# RBPZ_DynamixelMaxim.net
KiCad netlist of a schematic drawn in EAGLE
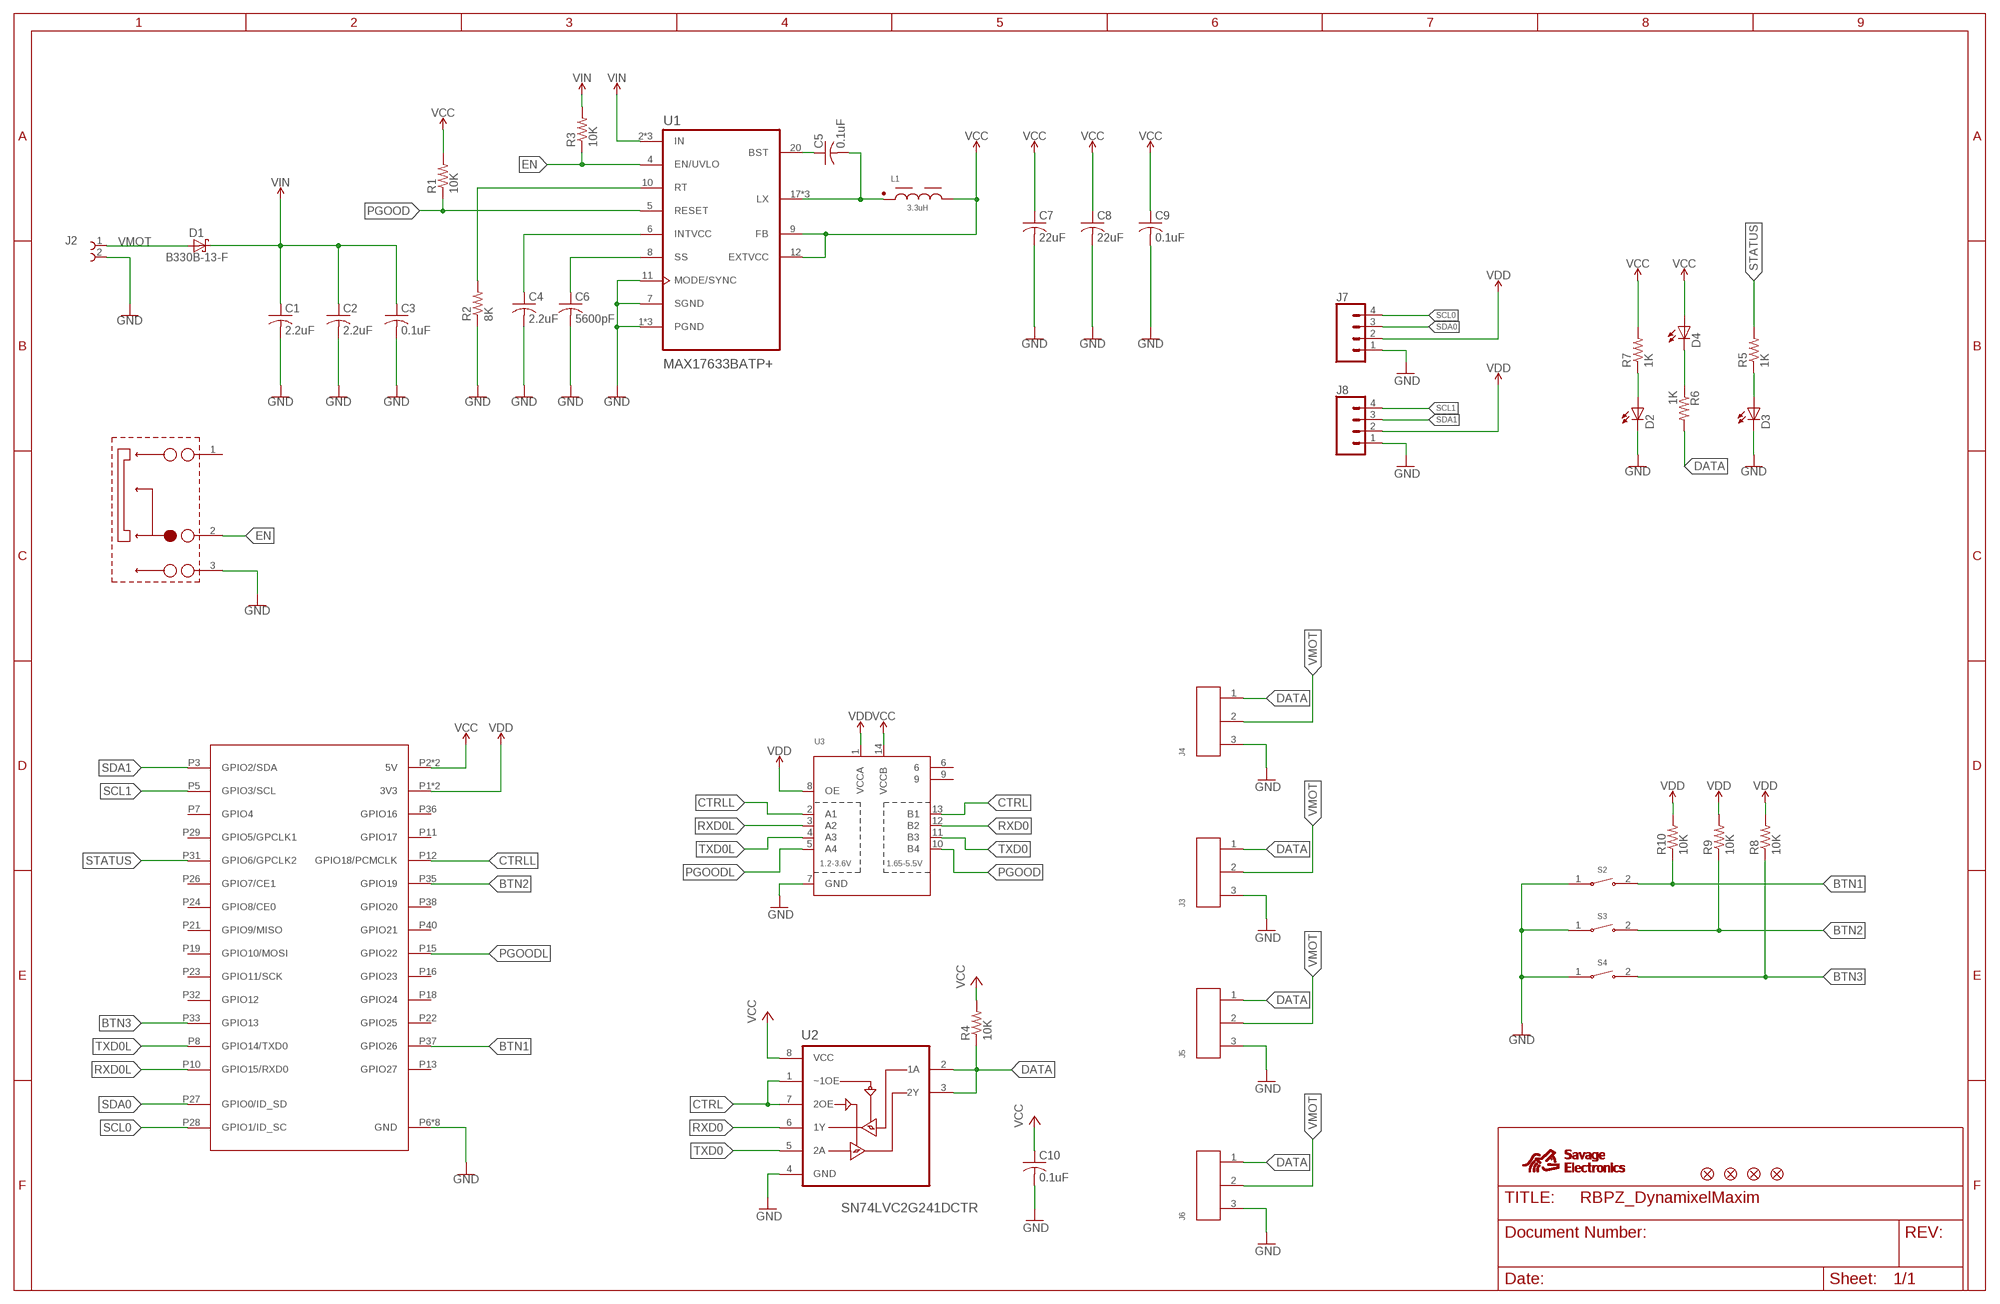
[diagram p0: schematic, sheet 1]

(export (version "E")
  (design (tool "Eeschema 10.0.6"))
  (components
    (comp (ref "C1")
      (value "2.2uF")
      (footprint "eagle-import:C1210")
      (libsource (lib "eagle-import") (part "C-USC1210"))
    )
    (comp (ref "C2")
      (value "2.2uF")
      (footprint "eagle-import:C1210")
      (libsource (lib "eagle-import") (part "C-USC1210"))
    )
    (comp (ref "C3")
      (value "0.1uF")
      (footprint "eagle-import:C0805")
      (libsource (lib "eagle-import") (part "C-USC0805"))
    )
    (comp (ref "C4")
      (value "2.2uF")
      (footprint "eagle-import:C1206")
      (libsource (lib "eagle-import") (part "C-USC1206"))
    )
    (comp (ref "C5")
      (value "0.1uF")
      (footprint "eagle-import:C0603")
      (libsource (lib "eagle-import") (part "C-USC0603"))
    )
    (comp (ref "C6")
      (value "5600pF")
      (footprint "eagle-import:C0805")
      (libsource (lib "eagle-import") (part "C-USC0805"))
    )
    (comp (ref "C7")
      (value "22uF")
      (footprint "eagle-import:C1210")
      (libsource (lib "eagle-import") (part "C-USC1210"))
    )
    (comp (ref "C8")
      (value "22uF")
      (footprint "eagle-import:C1210")
      (libsource (lib "eagle-import") (part "C-USC1210"))
    )
    (comp (ref "C9")
      (value "0.1uF")
      (footprint "eagle-import:C0805")
      (libsource (lib "eagle-import") (part "C-USC0805"))
    )
    (comp (ref "C10")
      (value "0.1uF")
      (footprint "eagle-import:C0603")
      (libsource (lib "eagle-import") (part "C-USC0603"))
    )
    (comp (ref "D1")
      (value "B330B-13-F")
      (footprint "eagle-import:DIONM4336X250N")
      (libsource (lib "eagle-import") (part "B330B-13-F"))
    )
    (comp (ref "D2")
      (value "LEDCHIP-LED0805")
      (footprint "eagle-import:CHIP-LED0805")
      (libsource (lib "eagle-import") (part "LEDCHIP-LED0805"))
    )
    (comp (ref "D3")
      (value "LEDCHIP-LED0805")
      (footprint "eagle-import:CHIP-LED0805")
      (libsource (lib "eagle-import") (part "LEDCHIP-LED0805"))
    )
    (comp (ref "D4")
      (value "LEDCHIP-LED0805")
      (footprint "eagle-import:CHIP-LED0805")
      (libsource (lib "eagle-import") (part "LEDCHIP-LED0805"))
    )
    (comp (ref "FID1")
      (value "FIDUCIAL\"\"")
      (footprint "eagle-import:FIDUCIAL_1MM")
      (libsource (lib "eagle-import") (part "FIDUCIAL{dblquote}{dblquote}"))
    )
    (comp (ref "FID2")
      (value "FIDUCIAL\"\"")
      (footprint "eagle-import:FIDUCIAL_1MM")
      (libsource (lib "eagle-import") (part "FIDUCIAL{dblquote}{dblquote}"))
    )
    (comp (ref "FID3")
      (value "FIDUCIAL\"\"")
      (footprint "eagle-import:FIDUCIAL_1MM")
      (libsource (lib "eagle-import") (part "FIDUCIAL{dblquote}{dblquote}"))
    )
    (comp (ref "FID4")
      (value "FIDUCIAL\"\"")
      (footprint "eagle-import:FIDUCIAL_1MM")
      (libsource (lib "eagle-import") (part "FIDUCIAL{dblquote}{dblquote}"))
    )
    (comp (ref "J1")
      (value "RBPZERO")
      (footprint "eagle-import:61004021821_RASPBERRYPIZERO")
      (libsource (lib "eagle-import") (part "RBPZERO"))
    )
    (comp (ref "J2")
      (value "691137910002")
      (footprint "eagle-import:691137910002")
      (libsource (lib "eagle-import") (part "691137910002"))
    )
    (comp (ref "J3")
      (value "64600311622")
      (footprint "eagle-import:64600311622")
      (libsource (lib "eagle-import") (part "64600311622"))
    )
    (comp (ref "J4")
      (value "64600311622")
      (footprint "eagle-import:64600311622")
      (libsource (lib "eagle-import") (part "64600311622"))
    )
    (comp (ref "J5")
      (value "64600311622")
      (footprint "eagle-import:64600311622")
      (libsource (lib "eagle-import") (part "64600311622"))
    )
    (comp (ref "J6")
      (value "64600311622")
      (footprint "eagle-import:64600311622")
      (libsource (lib "eagle-import") (part "64600311622"))
    )
    (comp (ref "J7")
      (value "CONN_04SMD2")
      (footprint "eagle-import:1X04_1MM_RA")
      (libsource (lib "eagle-import") (part "CONN_04SMD2"))
    )
    (comp (ref "J8")
      (value "CONN_04SMD2")
      (footprint "eagle-import:1X04_1MM_RA")
      (libsource (lib "eagle-import") (part "CONN_04SMD2"))
    )
    (comp (ref "L1")
      (value "3.3uH")
      (footprint "eagle-import:WE-SPC_48XX")
      (libsource (lib "eagle-import") (part "WE-SPC_4828_74408942012"))
    )
    (comp (ref "R1")
      (value "10K")
      (footprint "eagle-import:R0805")
      (libsource (lib "eagle-import") (part "R-US_R0805"))
    )
    (comp (ref "R2")
      (value "8K")
      (footprint "eagle-import:R0805")
      (libsource (lib "eagle-import") (part "R-US_R0805"))
    )
    (comp (ref "R3")
      (value "10K")
      (footprint "eagle-import:R0805")
      (libsource (lib "eagle-import") (part "R-US_R0805"))
    )
    (comp (ref "R4")
      (value "10K")
      (footprint "eagle-import:R0805")
      (libsource (lib "eagle-import") (part "R-US_R0805"))
    )
    (comp (ref "R5")
      (value "1K")
      (footprint "eagle-import:R0805")
      (libsource (lib "eagle-import") (part "R-US_R0805"))
    )
    (comp (ref "R6")
      (value "1K")
      (footprint "eagle-import:R0805")
      (libsource (lib "eagle-import") (part "R-US_R0805"))
    )
    (comp (ref "R7")
      (value "1K")
      (footprint "eagle-import:R0805")
      (libsource (lib "eagle-import") (part "R-US_R0805"))
    )
    (comp (ref "R8")
      (value "10K")
      (footprint "eagle-import:R0805")
      (libsource (lib "eagle-import") (part "R-US_R0805"))
    )
    (comp (ref "R9")
      (value "10K")
      (footprint "eagle-import:R0805")
      (libsource (lib "eagle-import") (part "R-US_R0805"))
    )
    (comp (ref "R10")
      (value "10K")
      (footprint "eagle-import:R0805")
      (libsource (lib "eagle-import") (part "R-US_R0805"))
    )
    (comp (ref "S1")
      (value "450404015514")
      (footprint "eagle-import:450404015514")
      (libsource (lib "eagle-import") (part "450404015514"))
    )
    (comp (ref "S2")
      (value "434123025826-2PIN")
      (footprint "eagle-import:434123025826-2PIN")
      (libsource (lib "eagle-import") (part "434123025826-2PIN"))
    )
    (comp (ref "S3")
      (value "434123025826-2PIN")
      (footprint "eagle-import:434123025826-2PIN")
      (libsource (lib "eagle-import") (part "434123025826-2PIN"))
    )
    (comp (ref "S4")
      (value "434123025826-2PIN")
      (footprint "eagle-import:434123025826-2PIN")
      (libsource (lib "eagle-import") (part "434123025826-2PIN"))
    )
    (comp (ref "U1")
      (value "MAX17633BATP+")
      (footprint "eagle-import:QFN50P400X400X80-21N")
      (fields (field (name "MF") "Maxim Integrated") (field (name "MP") "MAX32660GTP+T"))
      (libsource (lib "eagle-import") (part "MAX17633BATP+"))
    )
    (comp (ref "U2")
      (value "SN74LVC2G241DCTR")
      (footprint "eagle-import:SOP65P400X130-8N")
      (fields (field (name "MF") "Texas Instruments") (field (name "MP") "SN74LVC2G241"))
      (libsource (lib "eagle-import") (part "SN74LVC2G241"))
    )
    (comp (ref "U3")
      (value "TXB0104PWR")
      (footprint "eagle-import:TSSOP14")
      (libsource (lib "eagle-import") (part "TXB0104PWR"))
    )
  )
  (nets
    (net (code "1") (name "BTN1") (class "Default")
      (node (ref "J1") (pin "P37") (pinfunction "GPIO26_P37") (pintype "bidirectional"))
      (node (ref "R10") (pin "1") (pinfunction "1_1") (pintype "passive"))
      (node (ref "S2") (pin "2") (pinfunction "2_2") (pintype "passive"))
    )
    (net (code "2") (name "BTN2") (class "Default")
      (node (ref "J1") (pin "P35") (pinfunction "GPIO19_P35") (pintype "bidirectional"))
      (node (ref "R9") (pin "1") (pinfunction "1_1") (pintype "passive"))
      (node (ref "S3") (pin "2") (pinfunction "2_2") (pintype "passive"))
    )
    (net (code "3") (name "BTN3") (class "Default")
      (node (ref "J1") (pin "P33") (pinfunction "GPIO13_P33") (pintype "bidirectional"))
      (node (ref "R8") (pin "1") (pinfunction "1_1") (pintype "passive"))
      (node (ref "S4") (pin "2") (pinfunction "2_2") (pintype "passive"))
    )
    (net (code "4") (name "CTRL") (class "Default")
      (node (ref "U2") (pin "1") (pinfunction "~{1OE}_1") (pintype "input"))
      (node (ref "U2") (pin "7") (pinfunction "2OE_7") (pintype "input"))
      (node (ref "U3") (pin "13") (pinfunction "B1_13") (pintype "bidirectional"))
    )
    (net (code "5") (name "CTRLL") (class "Default")
      (node (ref "J1") (pin "P12") (pinfunction "GPIO18/PCMCLK_P12") (pintype "bidirectional"))
      (node (ref "U3") (pin "2") (pinfunction "A1_2") (pintype "bidirectional"))
    )
    (net (code "6") (name "DATA") (class "Default")
      (node (ref "J3") (pin "1") (pinfunction "1_1") (pintype "passive"))
      (node (ref "J4") (pin "1") (pinfunction "1_1") (pintype "passive"))
      (node (ref "J5") (pin "1") (pinfunction "1_1") (pintype "passive"))
      (node (ref "J6") (pin "1") (pinfunction "1_1") (pintype "passive"))
      (node (ref "R4") (pin "1") (pinfunction "1_1") (pintype "passive"))
      (node (ref "R6") (pin "2") (pinfunction "2_2") (pintype "passive"))
      (node (ref "U2") (pin "2") (pinfunction "1A_2") (pintype "input"))
      (node (ref "U2") (pin "3") (pinfunction "2Y_3") (pintype "output"))
    )
    (net (code "7") (name "EN") (class "Default")
      (node (ref "R3") (pin "1") (pinfunction "1_1") (pintype "passive"))
      (node (ref "S1") (pin "2") (pinfunction "2_2") (pintype "passive"))
      (node (ref "U1") (pin "4") (pinfunction "EN/UVLO_4") (pintype "power_in"))
    )
    (net (code "8") (name "GND") (class "Default")
      (node (ref "C1") (pin "2") (pinfunction "2_2") (pintype "passive"))
      (node (ref "C10") (pin "2") (pinfunction "2_2") (pintype "passive"))
      (node (ref "C2") (pin "2") (pinfunction "2_2") (pintype "passive"))
      (node (ref "C3") (pin "2") (pinfunction "2_2") (pintype "passive"))
      (node (ref "C4") (pin "2") (pinfunction "2_2") (pintype "passive"))
      (node (ref "C6") (pin "2") (pinfunction "2_2") (pintype "passive"))
      (node (ref "C7") (pin "2") (pinfunction "2_2") (pintype "passive"))
      (node (ref "C8") (pin "2") (pinfunction "2_2") (pintype "passive"))
      (node (ref "C9") (pin "2") (pinfunction "2_2") (pintype "passive"))
      (node (ref "D2") (pin "C") (pinfunction "C_C") (pintype "passive"))
      (node (ref "D3") (pin "C") (pinfunction "C_C") (pintype "passive"))
      (node (ref "J1") (pin "P14") (pinfunction "GND_P14") (pintype "bidirectional"))
      (node (ref "J1") (pin "P20") (pinfunction "GND_P20") (pintype "bidirectional"))
      (node (ref "J1") (pin "P25") (pinfunction "GND_P25") (pintype "bidirectional"))
      (node (ref "J1") (pin "P30") (pinfunction "GND_P30") (pintype "bidirectional"))
      (node (ref "J1") (pin "P34") (pinfunction "GND_P34") (pintype "bidirectional"))
      (node (ref "J1") (pin "P39") (pinfunction "GND_P39") (pintype "bidirectional"))
      (node (ref "J1") (pin "P6") (pinfunction "GND_P6") (pintype "bidirectional"))
      (node (ref "J1") (pin "P9") (pinfunction "GND_P9") (pintype "bidirectional"))
      (node (ref "J2") (pin "2") (pinfunction "2_2") (pintype "passive"))
      (node (ref "J3") (pin "3") (pinfunction "3_3") (pintype "passive"))
      (node (ref "J4") (pin "3") (pinfunction "3_3") (pintype "passive"))
      (node (ref "J5") (pin "3") (pinfunction "3_3") (pintype "passive"))
      (node (ref "J6") (pin "3") (pinfunction "3_3") (pintype "passive"))
      (node (ref "J7") (pin "1") (pinfunction "1_1") (pintype "passive"))
      (node (ref "J8") (pin "1") (pinfunction "1_1") (pintype "passive"))
      (node (ref "R2") (pin "1") (pinfunction "1_1") (pintype "passive"))
      (node (ref "S1") (pin "3") (pinfunction "3_3") (pintype "passive"))
      (node (ref "S2") (pin "1") (pinfunction "1_1") (pintype "passive"))
      (node (ref "S3") (pin "1") (pinfunction "1_1") (pintype "passive"))
      (node (ref "S4") (pin "1") (pinfunction "1_1") (pintype "passive"))
      (node (ref "U1") (pin "1") (pinfunction "PGND_1") (pintype "bidirectional"))
      (node (ref "U1") (pin "11") (pinfunction "MODE/SYNC_11") (pintype "input"))
      (node (ref "U1") (pin "15") (pinfunction "PGND_15") (pintype "bidirectional"))
      (node (ref "U1") (pin "21") (pinfunction "PGND_21") (pintype "bidirectional"))
      (node (ref "U1") (pin "7") (pinfunction "SGND_7") (pintype "bidirectional"))
      (node (ref "U2") (pin "4") (pinfunction "GND_4") (pintype "passive"))
      (node (ref "U3") (pin "7") (pinfunction "GND_7") (pintype "bidirectional"))
    )
    (net (code "9") (name "Net-(C5-Pad2)") (class "Default")
      (node (ref "C5") (pin "2") (pinfunction "2_2") (pintype "passive"))
      (node (ref "L1") (pin "1") (pinfunction "1_1") (pintype "passive"))
      (node (ref "U1") (pin "17") (pinfunction "LX_17") (pintype "bidirectional"))
      (node (ref "U1") (pin "18") (pinfunction "LX_18") (pintype "bidirectional"))
      (node (ref "U1") (pin "19") (pinfunction "LX_19") (pintype "bidirectional"))
    )
    (net (code "10") (name "Net-(D2-PadA)") (class "Default")
      (node (ref "D2") (pin "A") (pinfunction "A_A") (pintype "passive"))
      (node (ref "R7") (pin "1") (pinfunction "1_1") (pintype "passive"))
    )
    (net (code "11") (name "Net-(D3-PadA)") (class "Default")
      (node (ref "D3") (pin "A") (pinfunction "A_A") (pintype "passive"))
      (node (ref "R5") (pin "1") (pinfunction "1_1") (pintype "passive"))
    )
    (net (code "12") (name "Net-(D4-PadC)") (class "Default")
      (node (ref "D4") (pin "C") (pinfunction "C_C") (pintype "passive"))
      (node (ref "R6") (pin "1") (pinfunction "1_1") (pintype "passive"))
    )
    (net (code "13") (name "Net-(U1-BST)") (class "Default")
      (node (ref "C5") (pin "1") (pinfunction "1_1") (pintype "passive"))
      (node (ref "U1") (pin "20") (pinfunction "BST_20") (pintype "bidirectional"))
    )
    (net (code "14") (name "Net-(U1-INTVCC)") (class "Default")
      (node (ref "C4") (pin "1") (pinfunction "1_1") (pintype "passive"))
      (node (ref "U1") (pin "6") (pinfunction "INTVCC_6") (pintype "output"))
    )
    (net (code "15") (name "Net-(U1-RT)") (class "Default")
      (node (ref "R2") (pin "2") (pinfunction "2_2") (pintype "passive"))
      (node (ref "U1") (pin "10") (pinfunction "RT_10") (pintype "input"))
    )
    (net (code "16") (name "Net-(U1-SS)") (class "Default")
      (node (ref "C6") (pin "1") (pinfunction "1_1") (pintype "passive"))
      (node (ref "U1") (pin "8") (pinfunction "SS_8") (pintype "bidirectional"))
    )
    (net (code "17") (name "PGOOD") (class "Default")
      (node (ref "R1") (pin "1") (pinfunction "1_1") (pintype "passive"))
      (node (ref "U1") (pin "5") (pinfunction "RESET_5") (pintype "bidirectional"))
      (node (ref "U3") (pin "10") (pinfunction "B4_10") (pintype "bidirectional"))
    )
    (net (code "18") (name "PGOODL") (class "Default")
      (node (ref "J1") (pin "P15") (pinfunction "GPIO22_P15") (pintype "bidirectional"))
      (node (ref "U3") (pin "5") (pinfunction "A4_5") (pintype "bidirectional"))
    )
    (net (code "19") (name "RXD0") (class "Default")
      (node (ref "U2") (pin "6") (pinfunction "1Y_6") (pintype "output"))
      (node (ref "U3") (pin "12") (pinfunction "B2_12") (pintype "bidirectional"))
    )
    (net (code "20") (name "RXD0L") (class "Default")
      (node (ref "J1") (pin "P10") (pinfunction "GPIO15/RXD0_P10") (pintype "bidirectional"))
      (node (ref "U3") (pin "3") (pinfunction "A2_3") (pintype "bidirectional"))
    )
    (net (code "21") (name "SCL0") (class "Default")
      (node (ref "J1") (pin "P28") (pinfunction "GPIO1/ID_SC_P28") (pintype "bidirectional"))
      (node (ref "J7") (pin "4") (pinfunction "4_4") (pintype "passive"))
    )
    (net (code "22") (name "SCL1") (class "Default")
      (node (ref "J1") (pin "P5") (pinfunction "GPIO3/SCL_P5") (pintype "bidirectional"))
      (node (ref "J8") (pin "4") (pinfunction "4_4") (pintype "passive"))
    )
    (net (code "23") (name "SDA0") (class "Default")
      (node (ref "J1") (pin "P27") (pinfunction "GPIO0/ID_SD_P27") (pintype "bidirectional"))
      (node (ref "J7") (pin "3") (pinfunction "3_3") (pintype "passive"))
    )
    (net (code "24") (name "SDA1") (class "Default")
      (node (ref "J1") (pin "P3") (pinfunction "GPIO2/SDA_P3") (pintype "bidirectional"))
      (node (ref "J8") (pin "3") (pinfunction "3_3") (pintype "passive"))
    )
    (net (code "25") (name "STATUS") (class "Default")
      (node (ref "J1") (pin "P31") (pinfunction "GPIO6/GPCLK2_P31") (pintype "bidirectional"))
      (node (ref "R5") (pin "2") (pinfunction "2_2") (pintype "passive"))
    )
    (net (code "26") (name "TXD0") (class "Default")
      (node (ref "U2") (pin "5") (pinfunction "2A_5") (pintype "input"))
      (node (ref "U3") (pin "11") (pinfunction "B3_11") (pintype "bidirectional"))
    )
    (net (code "27") (name "TXD0L") (class "Default")
      (node (ref "J1") (pin "P8") (pinfunction "GPIO14/TXD0_P8") (pintype "bidirectional"))
      (node (ref "U3") (pin "4") (pinfunction "A3_4") (pintype "bidirectional"))
    )
    (net (code "28") (name "VCC") (class "Default")
      (node (ref "C10") (pin "1") (pinfunction "1_1") (pintype "passive"))
      (node (ref "C7") (pin "1") (pinfunction "1_1") (pintype "passive"))
      (node (ref "C8") (pin "1") (pinfunction "1_1") (pintype "passive"))
      (node (ref "C9") (pin "1") (pinfunction "1_1") (pintype "passive"))
      (node (ref "D4") (pin "A") (pinfunction "A_A") (pintype "passive"))
      (node (ref "J1") (pin "P2") (pinfunction "5V_P2") (pintype "bidirectional"))
      (node (ref "J1") (pin "P4") (pinfunction "5V_P4") (pintype "bidirectional"))
      (node (ref "L1") (pin "2") (pinfunction "2_2") (pintype "passive"))
      (node (ref "R1") (pin "2") (pinfunction "2_2") (pintype "passive"))
      (node (ref "R4") (pin "2") (pinfunction "2_2") (pintype "passive"))
      (node (ref "R7") (pin "2") (pinfunction "2_2") (pintype "passive"))
      (node (ref "U1") (pin "12") (pinfunction "EXTVCC_12") (pintype "bidirectional"))
      (node (ref "U1") (pin "9") (pinfunction "FB_9") (pintype "bidirectional"))
      (node (ref "U2") (pin "8") (pinfunction "VCC_8") (pintype "power_in"))
      (node (ref "U3") (pin "14") (pinfunction "VCCB_14") (pintype "bidirectional"))
    )
    (net (code "29") (name "VDD") (class "Default")
      (node (ref "J1") (pin "P1") (pinfunction "3V3_P1") (pintype "bidirectional"))
      (node (ref "J1") (pin "P17") (pinfunction "3V3_P17") (pintype "bidirectional"))
      (node (ref "J7") (pin "2") (pinfunction "2_2") (pintype "passive"))
      (node (ref "J8") (pin "2") (pinfunction "2_2") (pintype "passive"))
      (node (ref "R10") (pin "2") (pinfunction "2_2") (pintype "passive"))
      (node (ref "R8") (pin "2") (pinfunction "2_2") (pintype "passive"))
      (node (ref "R9") (pin "2") (pinfunction "2_2") (pintype "passive"))
      (node (ref "U3") (pin "1") (pinfunction "VCCA_1") (pintype "bidirectional"))
      (node (ref "U3") (pin "8") (pinfunction "OE_8") (pintype "bidirectional"))
    )
    (net (code "30") (name "VIN") (class "Default")
      (node (ref "C1") (pin "1") (pinfunction "1_1") (pintype "passive"))
      (node (ref "C2") (pin "1") (pinfunction "1_1") (pintype "passive"))
      (node (ref "C3") (pin "1") (pinfunction "1_1") (pintype "passive"))
      (node (ref "D1") (pin "1") (pinfunction "C_1") (pintype "passive"))
      (node (ref "R3") (pin "2") (pinfunction "2_2") (pintype "passive"))
      (node (ref "U1") (pin "14") (pinfunction "IN_14") (pintype "power_in"))
      (node (ref "U1") (pin "2") (pinfunction "IN_2") (pintype "power_in"))
      (node (ref "U1") (pin "3") (pinfunction "IN_3") (pintype "power_in"))
    )
    (net (code "31") (name "VMOT") (class "Default")
      (node (ref "D1") (pin "2") (pinfunction "A_2") (pintype "passive"))
      (node (ref "J2") (pin "1") (pinfunction "1_1") (pintype "passive"))
      (node (ref "J3") (pin "2") (pinfunction "2_2") (pintype "passive"))
      (node (ref "J4") (pin "2") (pinfunction "2_2") (pintype "passive"))
      (node (ref "J5") (pin "2") (pinfunction "2_2") (pintype "passive"))
      (node (ref "J6") (pin "2") (pinfunction "2_2") (pintype "passive"))
    )
    (net (code "32") (name "unconnected-(J1-GPIO4-PadP7)") (class "Default")
      (node (ref "J1") (pin "P7") (pinfunction "GPIO4_P7") (pintype "bidirectional"))
    )
    (net (code "33") (name "unconnected-(J1-GPIO5{slash}GPCLK1-PadP29)") (class "Default")
      (node (ref "J1") (pin "P29") (pinfunction "GPIO5/GPCLK1_P29") (pintype "bidirectional"))
    )
    (net (code "34") (name "unconnected-(J1-GPIO7{slash}CE1-PadP26)") (class "Default")
      (node (ref "J1") (pin "P26") (pinfunction "GPIO7/CE1_P26") (pintype "bidirectional"))
    )
    (net (code "35") (name "unconnected-(J1-GPIO8{slash}CE0-PadP24)") (class "Default")
      (node (ref "J1") (pin "P24") (pinfunction "GPIO8/CE0_P24") (pintype "bidirectional"))
    )
    (net (code "36") (name "unconnected-(J1-GPIO9{slash}MISO-PadP21)") (class "Default")
      (node (ref "J1") (pin "P21") (pinfunction "GPIO9/MISO_P21") (pintype "bidirectional"))
    )
    (net (code "37") (name "unconnected-(J1-GPIO10{slash}MOSI-PadP19)") (class "Default")
      (node (ref "J1") (pin "P19") (pinfunction "GPIO10/MOSI_P19") (pintype "bidirectional"))
    )
    (net (code "38") (name "unconnected-(J1-GPIO11{slash}SCK-PadP23)") (class "Default")
      (node (ref "J1") (pin "P23") (pinfunction "GPIO11/SCK_P23") (pintype "bidirectional"))
    )
    (net (code "39") (name "unconnected-(J1-GPIO12-PadP32)") (class "Default")
      (node (ref "J1") (pin "P32") (pinfunction "GPIO12_P32") (pintype "bidirectional"))
    )
    (net (code "40") (name "unconnected-(J1-GPIO16-PadP36)") (class "Default")
      (node (ref "J1") (pin "P36") (pinfunction "GPIO16_P36") (pintype "bidirectional"))
    )
    (net (code "41") (name "unconnected-(J1-GPIO17-PadP11)") (class "Default")
      (node (ref "J1") (pin "P11") (pinfunction "GPIO17_P11") (pintype "bidirectional"))
    )
    (net (code "42") (name "unconnected-(J1-GPIO20-PadP38)") (class "Default")
      (node (ref "J1") (pin "P38") (pinfunction "GPIO20_P38") (pintype "bidirectional"))
    )
    (net (code "43") (name "unconnected-(J1-GPIO21-PadP40)") (class "Default")
      (node (ref "J1") (pin "P40") (pinfunction "GPIO21_P40") (pintype "bidirectional"))
    )
    (net (code "44") (name "unconnected-(J1-GPIO23-PadP16)") (class "Default")
      (node (ref "J1") (pin "P16") (pinfunction "GPIO23_P16") (pintype "bidirectional"))
    )
    (net (code "45") (name "unconnected-(J1-GPIO24-PadP18)") (class "Default")
      (node (ref "J1") (pin "P18") (pinfunction "GPIO24_P18") (pintype "bidirectional"))
    )
    (net (code "46") (name "unconnected-(J1-GPIO25-PadP22)") (class "Default")
      (node (ref "J1") (pin "P22") (pinfunction "GPIO25_P22") (pintype "bidirectional"))
    )
    (net (code "47") (name "unconnected-(J1-GPIO27-PadP13)") (class "Default")
      (node (ref "J1") (pin "P13") (pinfunction "GPIO27_P13") (pintype "bidirectional"))
    )
    (net (code "48") (name "unconnected-(S1-Pad1)") (class "Default")
      (node (ref "S1") (pin "1") (pinfunction "1_1") (pintype "passive"))
    )
    (net (code "49") (name "unconnected-(U3-Pad6)") (class "Default")
      (node (ref "U3") (pin "6") (pinfunction "6_6") (pintype "bidirectional"))
    )
    (net (code "50") (name "unconnected-(U3-Pad9)") (class "Default")
      (node (ref "U3") (pin "9") (pinfunction "9_9") (pintype "bidirectional"))
    )
  )
)
